# PowerSupply.net
KiCad netlist of a schematic drawn in Altium Designer
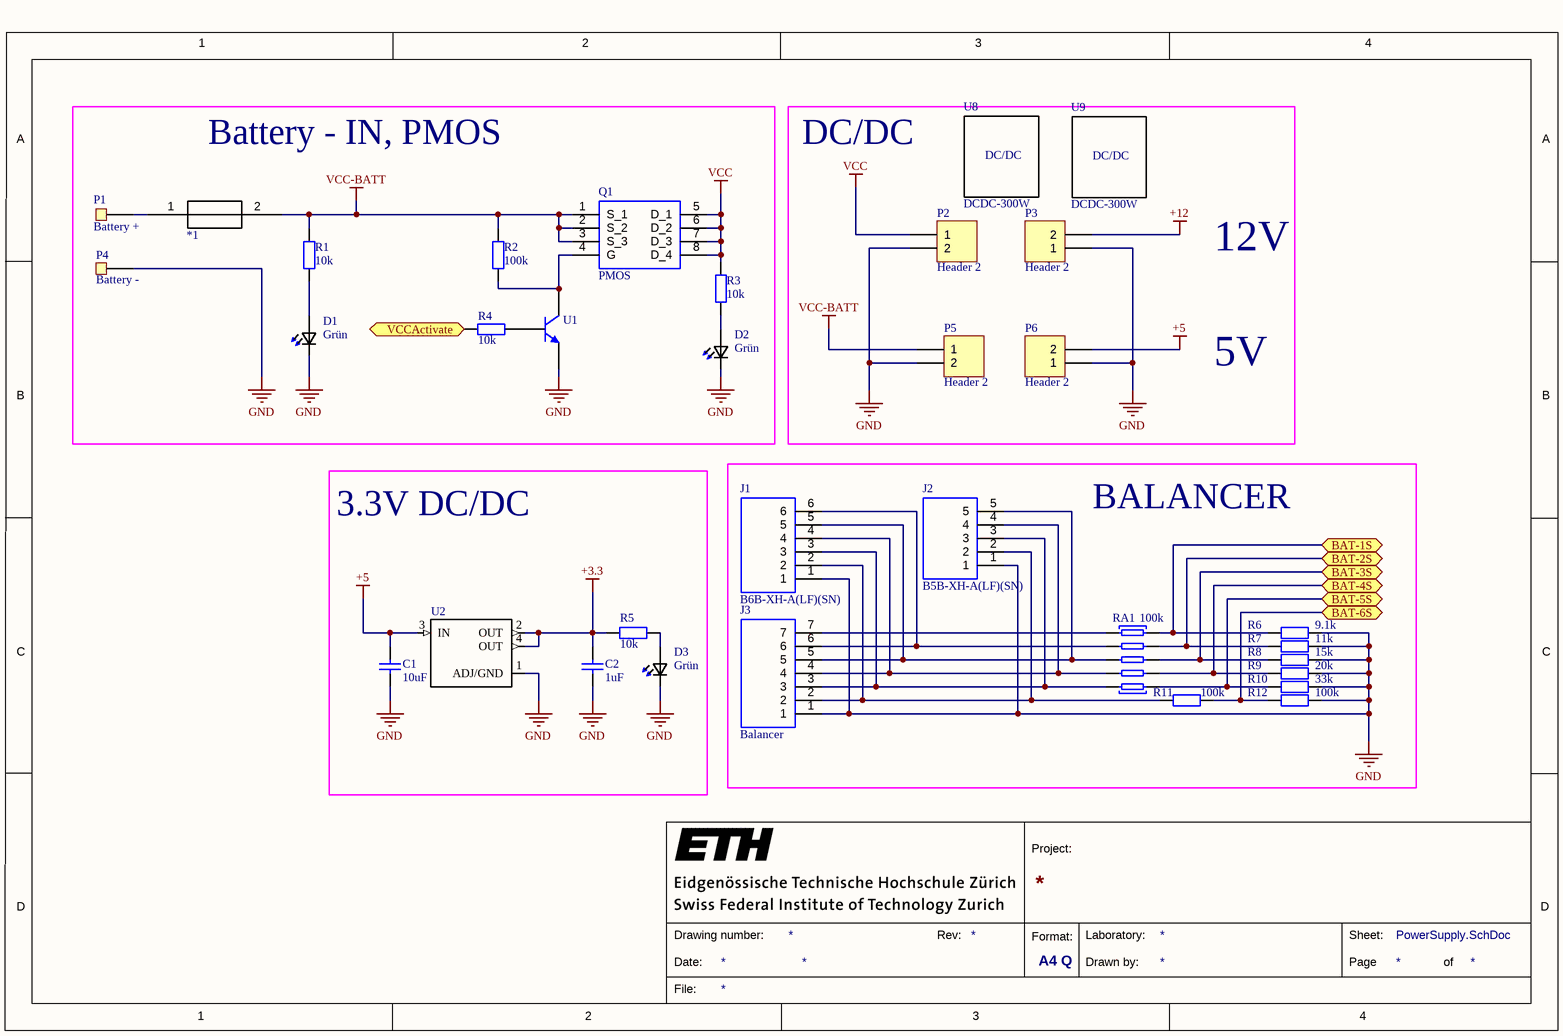
[diagram p0: PowerSupply.SchDoc]

(export (version "E")
  (design (tool "Eeschema 10.0.6"))
  (components
    (comp (ref "*1") (value "Fuse") (footprint "FUSE-3586KTR") (libsource (lib "Funk") (part "Fuse")))
    (comp (ref "C1")
      (value "10uF")
      (footprint "CAP_0805i_2012m -L")
      (description "capacitor")
      (libsource (lib "IDSC std generic parts") (part "Cap"))
    )
    (comp (ref "C2")
      (value "1uF")
      (footprint "CAP_0805i_2012m -L")
      (description "capacitor")
      (libsource (lib "IDSC std generic parts") (part "Cap"))
    )
    (comp (ref "D1")
      (value "Grün")
      (footprint "*0603")
      (description "LED; SMD; 0603; gr黱; 35mcd; 1.6x0.8x0.55mm; 130掳; 2梅2.V; 20mA")
      (fields (field (name "MP") "LTST-C191KGKT") (field (name "DIGI-KEY_PART_NUMBER") "160-1446-1-ND"))
      (libsource (lib "Funk") (part "LTST-C191KGKT"))
    )
    (comp (ref "D2")
      (value "Grün")
      (footprint "*0603")
      (description "LED; SMD; 0603; gr黱; 35mcd; 1.6x0.8x0.55mm; 130掳; 2梅2.V; 20mA")
      (fields (field (name "MP") "LTST-C191KGKT") (field (name "DIGI-KEY_PART_NUMBER") "160-1446-1-ND"))
      (libsource (lib "Funk") (part "LTST-C191KGKT"))
    )
    (comp (ref "D3")
      (value "Grün")
      (footprint "*0603")
      (description "LED; SMD; 0603; gr黱; 35mcd; 1.6x0.8x0.55mm; 130掳; 2梅2.V; 20mA")
      (fields (field (name "MP") "LTST-C191KGKT") (field (name "DIGI-KEY_PART_NUMBER") "160-1446-1-ND"))
      (libsource (lib "Funk") (part "LTST-C191KGKT"))
    )
    (comp (ref "J1")
      (value "B6B-XH-A(LF)(SN)")
      (footprint "SHDR6W64P0X250_1X6_1740X575X700P")
      (description "XH connector, 6 way")
      (fields (field (name "RS PART NUMBER") "8201563P"))
      (libsource (lib "Funk") (part "B6B-XH-A(LF)(SN)"))
    )
    (comp (ref "J2")
      (value "B5B-XH-A(LF)(SN)")
      (footprint "SHDR5W64P0X250_1X5_1490X575X700P")
      (description "XH connector, 5 way")
      (fields (field (name "RS PART NUMBER") "8201560P"))
      (libsource (lib "Funk") (part "B5B-XH-A(LF)(SN)"))
    )
    (comp (ref "J3")
      (value "Balancer")
      (footprint "SHDR7W64P0X250_1X7_1990X575X700P")
      (fields
        (field (name "MANUFACTURER_PART_NUMBER") "B7B-XH-A(LF)(SN)")
        (field (name "RS PART NUMBER") "8201567P")
      )
      (libsource (lib "Funk") (part "B7B-XH-A(LF)(SN)"))
    )
    (comp (ref "P1")
      (value "Battery +")
      (footprint "PIN1")
      (description "Single Pad or Testpoint")
      (libsource (lib "IDSC std connectors") (part "Pad"))
    )
    (comp (ref "P2")
      (value "Header 2")
      (footprint "3.5MM Phoenix Contact 1984617")
      (description "Header, 2-Pin")
      (libsource (lib "IDSC std connectors") (part "Header 2"))
    )
    (comp (ref "P3")
      (value "Header 2")
      (footprint "3.5MM Phoenix Contact 1984617")
      (description "Header, 2-Pin")
      (libsource (lib "") (part "Header 2_1"))
    )
    (comp (ref "P4")
      (value "Battery -")
      (footprint "PIN1")
      (description "Single Pad or Testpoint")
      (libsource (lib "IDSC std connectors") (part "Pad"))
    )
    (comp (ref "P5")
      (value "Header 2")
      (footprint "3.5MM Phoenix Contact 1984617")
      (description "Header, 2-Pin")
      (libsource (lib "IDSC std connectors") (part "Header 2"))
    )
    (comp (ref "P6")
      (value "Header 2")
      (footprint "3.5MM Phoenix Contact 1984617")
      (description "Header, 2-Pin")
      (libsource (lib "") (part "Header 2_1"))
    )
    (comp (ref "Q1")
      (value "PMOS")
      (footprint "SIS862DNT1GE3")
      (description "P-Channel MOSFET, 35 A, 20 V, 8-Pin PowerPAK 1212 Vishay")
      (fields
        (field (name "MANUFACTURER_PART_NUMBER") "SI7615ADN-T1-GE3")
        (field (name "MOUSER PART NUMBER") "78-SI7615ADN-T1-GE3")
      )
      (libsource (lib "Funk") (part "SI7615ADN-T1-GE3"))
    )
    (comp (ref "R1")
      (value "10k")
      (footprint "RES_0805i_2012m -N")
      (description "Resistor")
      (libsource (lib "") (part "Res_1"))
    )
    (comp (ref "R2")
      (value "100k")
      (footprint "RES_0805i_2012m -N")
      (description "Resistor")
      (libsource (lib "") (part "Res_1"))
    )
    (comp (ref "R3")
      (value "10k")
      (footprint "RES_0805i_2012m -N")
      (description "Resistor")
      (libsource (lib "") (part "Res_1"))
    )
    (comp (ref "R4")
      (value "10k")
      (footprint "RES_0805i_2012m -N")
      (description "Resistor")
      (libsource (lib "IDSC std generic parts") (part "Res"))
    )
    (comp (ref "R5")
      (value "10k")
      (footprint "RES_0805i_2012m -N")
      (description "Resistor")
      (libsource (lib "IDSC std generic parts") (part "Res"))
    )
    (comp (ref "R6")
      (value "9.1k")
      (footprint "RES_0805i_2012m -N")
      (description "Resistor")
      (libsource (lib "IDSC std generic parts") (part "Res"))
    )
    (comp (ref "R7")
      (value "11k")
      (footprint "RES_0805i_2012m -N")
      (description "Resistor")
      (libsource (lib "IDSC std generic parts") (part "Res"))
    )
    (comp (ref "R8")
      (value "15k")
      (footprint "RES_0805i_2012m -N")
      (description "Resistor")
      (libsource (lib "IDSC std generic parts") (part "Res"))
    )
    (comp (ref "R9")
      (value "20k")
      (footprint "RES_0805i_2012m -N")
      (description "Resistor")
      (libsource (lib "IDSC std generic parts") (part "Res"))
    )
    (comp (ref "R10")
      (value "33k")
      (footprint "RES_0805i_2012m -N")
      (description "Resistor")
      (libsource (lib "IDSC std generic parts") (part "Res"))
    )
    (comp (ref "R11")
      (value "100k")
      (footprint "RES_0805i_2012m -N")
      (description "Resistor")
      (libsource (lib "IDSC std generic parts") (part "Res"))
    )
    (comp (ref "R12")
      (value "100k")
      (footprint "RES_0805i_2012m -N")
      (description "Resistor")
      (libsource (lib "IDSC std generic parts") (part "Res"))
    )
    (comp (ref "RA1")
      (value "100k")
      (footprint "*SIP-10")
      (description "Isolated Resistor Network")
      (libsource (lib "Funk") (part "Res Array  5"))
    )
    (comp (ref "U1")
      (value "Part Number: MMBT3904-7-F")
      (footprint "SOT-23-M")
      (description "No Description Available")
      (fields
        (field (name "MANUFACTURER_PART_NUMBER") "MMBT3904-7-F")
        (field (name "COPYRIGHT") "Copyright (C) 2018 Accelerated Designs. All rights reserved")
      )
      (libsource (lib "Funk") (part "MMBT3904-7-F"))
    )
    (comp (ref "U2")
      (value "AZ1117EH-3.3TRG1")
      (footprint "*SOT230P700X180-4N")
      (description "Ldo.Vreg Pos 3, 3v 1a Sot223")
      (fields
        (field (name "MF") "Diodes Inc.")
        (field (name "DIGI-KEY_PART_NUMBER") "AZ1117EH-3.3TRG1DICT-ND")
      )
      (libsource (lib "Funk") (part "AZ1117EH-3.3TRG1"))
    )
    (comp (ref "U8")
      (value "DCDC-300W")
      (footprint "DCDC-300W")
      (description "6-36V 20A")
      (libsource (lib "Funk") (part "DCDC-300W"))
    )
    (comp (ref "U9")
      (value "DCDC-300W")
      (footprint "DCDC-300W")
      (description "6-36V 20A")
      (libsource (lib "Funk") (part "DCDC-300W"))
    )
  )
  (nets
    (net (code "1") (name "+3.3") (class "Default")
      (node (ref "C2") (pin "2") (pinfunction "2_2") (pintype "passive"))
      (node (ref "R5") (pin "2") (pinfunction "2_2") (pintype "passive"))
      (node (ref "U2") (pin "2") (pinfunction "OUT_2") (pintype "output"))
      (node (ref "U2") (pin "4") (pinfunction "OUT_4") (pintype "output"))
    )
    (net (code "2") (name "+5") (class "Default")
      (node (ref "C1") (pin "2") (pinfunction "2_2") (pintype "passive"))
      (node (ref "P6") (pin "2") (pinfunction "2_2") (pintype "passive"))
      (node (ref "U2") (pin "3") (pinfunction "IN_3") (pintype "input"))
    )
    (net (code "3") (name "+12") (class "Default")
      (node (ref "P3") (pin "2") (pinfunction "2_2") (pintype "passive"))
    )
    (net (code "4") (name "/BAT-1S") (class "Default")
      (node (ref "R6") (pin "2") (pinfunction "2_2") (pintype "passive"))
      (node (ref "RA1") (pin "2") (pinfunction "2_2") (pintype "passive"))
    )
    (net (code "5") (name "/BAT-2S") (class "Default")
      (node (ref "R7") (pin "2") (pinfunction "2_2") (pintype "passive"))
      (node (ref "RA1") (pin "4") (pinfunction "4_4") (pintype "passive"))
    )
    (net (code "6") (name "/BAT-3S") (class "Default")
      (node (ref "R8") (pin "2") (pinfunction "2_2") (pintype "passive"))
      (node (ref "RA1") (pin "6") (pinfunction "6_6") (pintype "passive"))
    )
    (net (code "7") (name "/BAT-4S") (class "Default")
      (node (ref "R9") (pin "2") (pinfunction "2_2") (pintype "passive"))
      (node (ref "RA1") (pin "8") (pinfunction "8_8") (pintype "passive"))
    )
    (net (code "8") (name "/BAT-5S") (class "Default")
      (node (ref "R10") (pin "2") (pinfunction "2_2") (pintype "passive"))
      (node (ref "RA1") (pin "10") (pinfunction "10_10") (pintype "passive"))
    )
    (net (code "9") (name "/BAT-6S") (class "Default")
      (node (ref "R11") (pin "1") (pinfunction "1_1") (pintype "passive"))
      (node (ref "R12") (pin "2") (pinfunction "2_2") (pintype "passive"))
    )
    (net (code "10") (name "/VCCActivate") (class "Default")
      (node (ref "R4") (pin "2") (pinfunction "2_2") (pintype "passive"))
    )
    (net (code "11") (name "GND") (class "Default")
      (node (ref "C1") (pin "1") (pinfunction "1_1") (pintype "passive"))
      (node (ref "C2") (pin "1") (pinfunction "1_1") (pintype "passive"))
      (node (ref "D1") (pin "1") (pinfunction "K2_1") (pintype "passive"))
      (node (ref "D2") (pin "1") (pinfunction "K2_1") (pintype "passive"))
      (node (ref "D3") (pin "1") (pinfunction "K2_1") (pintype "passive"))
      (node (ref "J1") (pin "1") (pinfunction "1_1") (pintype "passive"))
      (node (ref "J2") (pin "1") (pinfunction "1_1") (pintype "passive"))
      (node (ref "J3") (pin "1") (pinfunction "1_1") (pintype "passive"))
      (node (ref "P2") (pin "2") (pinfunction "2_2") (pintype "passive"))
      (node (ref "P3") (pin "1") (pinfunction "1_1") (pintype "passive"))
      (node (ref "P4") (pin "1") (pinfunction "1_1") (pintype "passive"))
      (node (ref "P5") (pin "2") (pinfunction "2_2") (pintype "passive"))
      (node (ref "P6") (pin "1") (pinfunction "1_1") (pintype "passive"))
      (node (ref "R10") (pin "1") (pinfunction "1_1") (pintype "passive"))
      (node (ref "R12") (pin "1") (pinfunction "1_1") (pintype "passive"))
      (node (ref "R6") (pin "1") (pinfunction "1_1") (pintype "passive"))
      (node (ref "R7") (pin "1") (pinfunction "1_1") (pintype "passive"))
      (node (ref "R8") (pin "1") (pinfunction "1_1") (pintype "passive"))
      (node (ref "R9") (pin "1") (pinfunction "1_1") (pintype "passive"))
      (node (ref "U1") (pin "2") (pinfunction "E_2") (pintype "passive"))
      (node (ref "U2") (pin "1") (pinfunction "ADJ/GND_1") (pintype "power_in"))
    )
    (net (code "12") (name "Net-(*1-Pad1)") (class "Default")
      (node (ref "*1") (pin "1") (pinfunction "1_1") (pintype "passive"))
      (node (ref "P1") (pin "1") (pinfunction "1_1") (pintype "passive"))
    )
    (net (code "13") (name "Net-(D1-A2)") (class "Default")
      (node (ref "D1") (pin "2") (pinfunction "A2_2") (pintype "passive"))
      (node (ref "R1") (pin "1") (pinfunction "1_1") (pintype "passive"))
    )
    (net (code "14") (name "Net-(D2-A2)") (class "Default")
      (node (ref "D2") (pin "2") (pinfunction "A2_2") (pintype "passive"))
      (node (ref "R3") (pin "1") (pinfunction "1_1") (pintype "passive"))
    )
    (net (code "15") (name "Net-(D3-A2)") (class "Default")
      (node (ref "D3") (pin "2") (pinfunction "A2_2") (pintype "passive"))
      (node (ref "R5") (pin "1") (pinfunction "1_1") (pintype "passive"))
    )
    (net (code "16") (name "Net-(J1-Pad2)") (class "Default")
      (node (ref "J1") (pin "2") (pinfunction "2_2") (pintype "passive"))
      (node (ref "J2") (pin "2") (pinfunction "2_2") (pintype "passive"))
      (node (ref "J3") (pin "2") (pinfunction "2_2") (pintype "passive"))
      (node (ref "R11") (pin "2") (pinfunction "2_2") (pintype "passive"))
    )
    (net (code "17") (name "Net-(J1-Pad3)") (class "Default")
      (node (ref "J1") (pin "3") (pinfunction "3_3") (pintype "passive"))
      (node (ref "J2") (pin "3") (pinfunction "3_3") (pintype "passive"))
      (node (ref "J3") (pin "3") (pinfunction "3_3") (pintype "passive"))
      (node (ref "RA1") (pin "9") (pinfunction "9_9") (pintype "passive"))
    )
    (net (code "18") (name "Net-(J1-Pad4)") (class "Default")
      (node (ref "J1") (pin "4") (pinfunction "4_4") (pintype "passive"))
      (node (ref "J2") (pin "4") (pinfunction "4_4") (pintype "passive"))
      (node (ref "J3") (pin "4") (pinfunction "4_4") (pintype "passive"))
      (node (ref "RA1") (pin "7") (pinfunction "7_7") (pintype "passive"))
    )
    (net (code "19") (name "Net-(J1-Pad5)") (class "Default")
      (node (ref "J1") (pin "5") (pinfunction "5_5") (pintype "passive"))
      (node (ref "J2") (pin "5") (pinfunction "5_5") (pintype "passive"))
      (node (ref "J3") (pin "5") (pinfunction "5_5") (pintype "passive"))
      (node (ref "RA1") (pin "5") (pinfunction "5_5") (pintype "passive"))
    )
    (net (code "20") (name "Net-(J1-Pad6)") (class "Default")
      (node (ref "J1") (pin "6") (pinfunction "6_6") (pintype "passive"))
      (node (ref "J3") (pin "6") (pinfunction "6_6") (pintype "passive"))
      (node (ref "RA1") (pin "3") (pinfunction "3_3") (pintype "passive"))
    )
    (net (code "21") (name "Net-(J3-Pad7)") (class "Default")
      (node (ref "J3") (pin "7") (pinfunction "7_7") (pintype "passive"))
      (node (ref "RA1") (pin "1") (pinfunction "1_1") (pintype "passive"))
    )
    (net (code "22") (name "Net-(Q1-G)") (class "Default")
      (node (ref "Q1") (pin "4") (pinfunction "G_4") (pintype "passive"))
      (node (ref "R2") (pin "1") (pinfunction "1_1") (pintype "passive"))
      (node (ref "U1") (pin "3") (pinfunction "C_3") (pintype "passive"))
    )
    (net (code "23") (name "Net-(U1-B)") (class "Default")
      (node (ref "R4") (pin "1") (pinfunction "1_1") (pintype "passive"))
      (node (ref "U1") (pin "1") (pinfunction "B_1") (pintype "passive"))
    )
    (net (code "24") (name "VCC") (class "Default")
      (node (ref "P2") (pin "1") (pinfunction "1_1") (pintype "passive"))
      (node (ref "Q1") (pin "5") (pinfunction "D_1_5") (pintype "passive"))
      (node (ref "Q1") (pin "6") (pinfunction "D_2_6") (pintype "passive"))
      (node (ref "Q1") (pin "7") (pinfunction "D_3_7") (pintype "passive"))
      (node (ref "Q1") (pin "8") (pinfunction "D_4_8") (pintype "passive"))
      (node (ref "R3") (pin "2") (pinfunction "2_2") (pintype "passive"))
    )
    (net (code "25") (name "VCC-BATT") (class "Default")
      (node (ref "*1") (pin "2") (pinfunction "2_2") (pintype "passive"))
      (node (ref "P5") (pin "1") (pinfunction "1_1") (pintype "passive"))
      (node (ref "Q1") (pin "1") (pinfunction "S_1_1") (pintype "passive"))
      (node (ref "Q1") (pin "2") (pinfunction "S_2_2") (pintype "passive"))
      (node (ref "Q1") (pin "3") (pinfunction "S_3_3") (pintype "passive"))
      (node (ref "R1") (pin "2") (pinfunction "2_2") (pintype "passive"))
      (node (ref "R2") (pin "2") (pinfunction "2_2") (pintype "passive"))
    )
  )
)
